# ngptv-lite.net
KiCad netlist of a schematic drawn in EAGLE
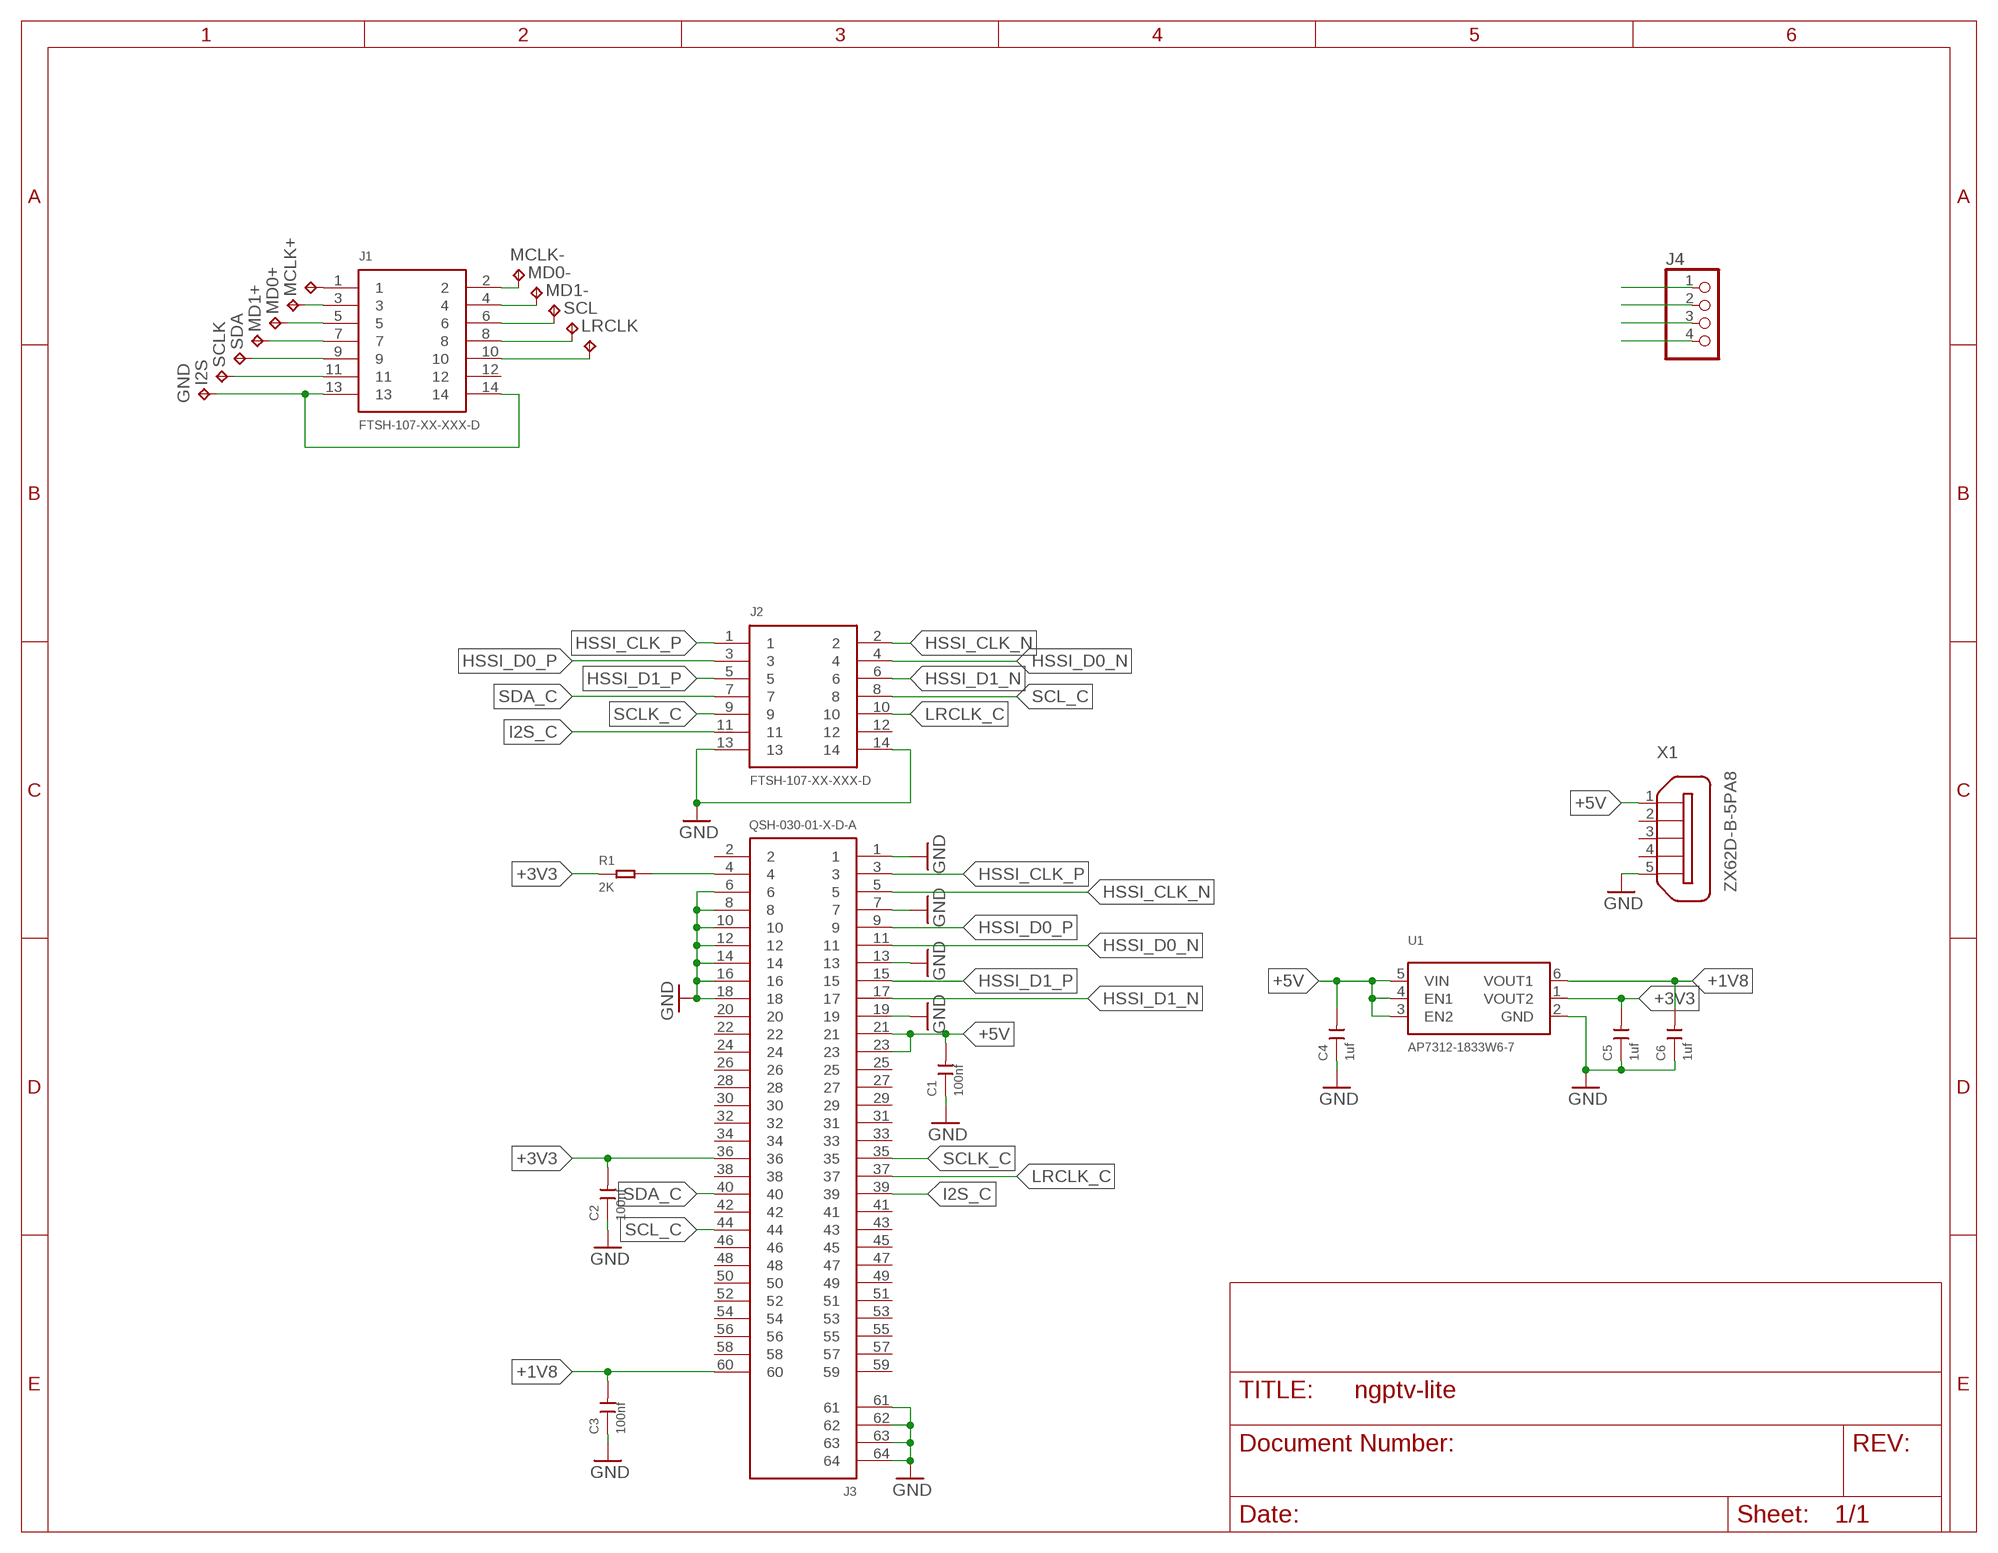
[diagram p0: schematic, sheet 1]

(export (version "E")
  (design (tool "Eeschema 10.0.6"))
  (components
    (comp (ref "C1")
      (value "100nf")
      (footprint "eagle-import:C0603")
      (fields (field (name "MPN") "CC0603KRX7R9BB104"))
      (libsource (lib "eagle-import") (part "CERAMIC-100NF-50V-10%-X7R(0603)"))
    )
    (comp (ref "C2")
      (value "100nf")
      (footprint "eagle-import:C0603")
      (fields (field (name "MPN") "CC0603KRX7R9BB104"))
      (libsource (lib "eagle-import") (part "CERAMIC-100NF-50V-10%-X7R(0603)"))
    )
    (comp (ref "C3")
      (value "100nf")
      (footprint "eagle-import:C0603")
      (fields (field (name "MPN") "CC0603KRX7R9BB104"))
      (libsource (lib "eagle-import") (part "CERAMIC-100NF-50V-10%-X7R(0603)"))
    )
    (comp (ref "C4")
      (value "1uf")
      (footprint "eagle-import:C0603")
      (fields (field (name "MPN") "CC0603KRX7R8BB105"))
      (libsource (lib "eagle-import") (part "CERAMIC-1UF-25V-10%-X7R(0603)"))
    )
    (comp (ref "C5")
      (value "1uf")
      (footprint "eagle-import:C0603")
      (fields (field (name "MPN") "CC0603KRX7R8BB105"))
      (libsource (lib "eagle-import") (part "CERAMIC-1UF-25V-10%-X7R(0603)"))
    )
    (comp (ref "C6")
      (value "1uf")
      (footprint "eagle-import:C0603")
      (fields (field (name "MPN") "CC0603KRX7R8BB105"))
      (libsource (lib "eagle-import") (part "CERAMIC-1UF-25V-10%-X7R(0603)"))
    )
    (comp (ref "GND")
      (value "TPTP14R")
      (footprint "eagle-import:TP14R")
      (libsource (lib "eagle-import") (part "TPTP14R"))
    )
    (comp (ref "I2S")
      (value "TPTP12R")
      (footprint "eagle-import:TP12R")
      (libsource (lib "eagle-import") (part "TPTP12R"))
    )
    (comp (ref "J1")
      (value "FTSH-107-XX-XXX-D")
      (footprint "eagle-import:FTSH-107-XX-XXX-D")
      (libsource (lib "eagle-import") (part "FTSH-107-XX-XXX-D"))
    )
    (comp (ref "J2")
      (value "FTSH-107-XX-XXX-D")
      (footprint "eagle-import:FTSH-107-XX-XXX-D")
      (libsource (lib "eagle-import") (part "FTSH-107-XX-XXX-D"))
    )
    (comp (ref "J3")
      (value "QSH-030-01-X-D-A")
      (footprint "eagle-import:QSH-030-01-X-D-A")
      (libsource (lib "eagle-import") (part "QSH-030-01-X-D-A"))
    )
    (comp (ref "J4")
      (value "PINHD-1X4")
      (footprint "eagle-import:1X04")
      (libsource (lib "eagle-import") (part "PINHD-1X4"))
    )
    (comp (ref "LRCLK")
      (value "TPTP12R")
      (footprint "eagle-import:TP12R")
      (libsource (lib "eagle-import") (part "TPTP12R"))
    )
    (comp (ref "MCLK+")
      (value "TPTP12R")
      (footprint "eagle-import:TP12R")
      (libsource (lib "eagle-import") (part "TPTP12R"))
    )
    (comp (ref "MCLK-")
      (value "TPTP12R")
      (footprint "eagle-import:TP12R")
      (libsource (lib "eagle-import") (part "TPTP12R"))
    )
    (comp (ref "MD0+")
      (value "TPTP12R")
      (footprint "eagle-import:TP12R")
      (libsource (lib "eagle-import") (part "TPTP12R"))
    )
    (comp (ref "MD0-")
      (value "TPTP12R")
      (footprint "eagle-import:TP12R")
      (libsource (lib "eagle-import") (part "TPTP12R"))
    )
    (comp (ref "MD1+")
      (value "TPTP12R")
      (footprint "eagle-import:TP12R")
      (libsource (lib "eagle-import") (part "TPTP12R"))
    )
    (comp (ref "MD1-")
      (value "TPTP12R")
      (footprint "eagle-import:TP12R")
      (libsource (lib "eagle-import") (part "TPTP12R"))
    )
    (comp (ref "R1")
      (value "2K")
      (footprint "eagle-import:R0603")
      (fields (field (name "MPN") "RC0603FR-072KL"))
      (libsource (lib "eagle-import") (part "SMD-RES-2K-1%-1/10W(0603)"))
    )
    (comp (ref "SCL")
      (value "TPTP12R")
      (footprint "eagle-import:TP12R")
      (libsource (lib "eagle-import") (part "TPTP12R"))
    )
    (comp (ref "SCLK")
      (value "TPTP12R")
      (footprint "eagle-import:TP12R")
      (libsource (lib "eagle-import") (part "TPTP12R"))
    )
    (comp (ref "SDA")
      (value "TPTP12R")
      (footprint "eagle-import:TP12R")
      (libsource (lib "eagle-import") (part "TPTP12R"))
    )
    (comp (ref "U1")
      (value "AP7312-1833W6-7")
      (footprint "eagle-import:SOT95P280X145-6N")
      (libsource (lib "eagle-import") (part "AP7312"))
    )
    (comp (ref "X1")
      (value "ZX62D-B-5PA8")
      (footprint "eagle-import:ZX62D-B-5PA8")
      (fields (field (name "MF") "Hirose"))
      (libsource (lib "eagle-import") (part "ZX62D-B-5PA8"))
    )
  )
  (nets
    (net (code "1") (name "+1V8") (class "Default")
      (node (ref "C3") (pin "2") (pinfunction "2_2") (pintype "passive"))
      (node (ref "C6") (pin "2") (pinfunction "2_2") (pintype "passive"))
      (node (ref "J3") (pin "60") (pinfunction "60_60") (pintype "bidirectional"))
      (node (ref "U1") (pin "6") (pinfunction "VOUT1_6") (pintype "power_in"))
    )
    (net (code "2") (name "+3V3") (class "Default")
      (node (ref "C2") (pin "2") (pinfunction "2_2") (pintype "passive"))
      (node (ref "C5") (pin "2") (pinfunction "2_2") (pintype "passive"))
      (node (ref "J3") (pin "36") (pinfunction "36_36") (pintype "bidirectional"))
      (node (ref "R1") (pin "1") (pinfunction "1_1") (pintype "passive"))
      (node (ref "U1") (pin "1") (pinfunction "VOUT2_1") (pintype "power_in"))
    )
    (net (code "3") (name "+5V") (class "Default")
      (node (ref "C1") (pin "2") (pinfunction "2_2") (pintype "passive"))
      (node (ref "C4") (pin "2") (pinfunction "2_2") (pintype "passive"))
      (node (ref "J3") (pin "21") (pinfunction "21_21") (pintype "bidirectional"))
      (node (ref "J3") (pin "23") (pinfunction "23_23") (pintype "bidirectional"))
      (node (ref "J4") (pin "1") (pinfunction "1_1") (pintype "passive"))
      (node (ref "U1") (pin "3") (pinfunction "EN2_3") (pintype "bidirectional"))
      (node (ref "U1") (pin "4") (pinfunction "EN1_4") (pintype "bidirectional"))
      (node (ref "U1") (pin "5") (pinfunction "VIN_5") (pintype "power_in"))
      (node (ref "X1") (pin "1") (pinfunction "1_1") (pintype "passive"))
    )
    (net (code "4") (name "GND") (class "Default")
      (node (ref "C1") (pin "1") (pinfunction "1_1") (pintype "passive"))
      (node (ref "C2") (pin "1") (pinfunction "1_1") (pintype "passive"))
      (node (ref "C3") (pin "1") (pinfunction "1_1") (pintype "passive"))
      (node (ref "C4") (pin "1") (pinfunction "1_1") (pintype "passive"))
      (node (ref "C5") (pin "1") (pinfunction "1_1") (pintype "passive"))
      (node (ref "C6") (pin "1") (pinfunction "1_1") (pintype "passive"))
      (node (ref "J2") (pin "13") (pinfunction "13_13") (pintype "bidirectional"))
      (node (ref "J2") (pin "14") (pinfunction "14_14") (pintype "bidirectional"))
      (node (ref "J3") (pin "1") (pinfunction "1_1") (pintype "bidirectional"))
      (node (ref "J3") (pin "10") (pinfunction "10_10") (pintype "bidirectional"))
      (node (ref "J3") (pin "12") (pinfunction "12_12") (pintype "bidirectional"))
      (node (ref "J3") (pin "13") (pinfunction "13_13") (pintype "bidirectional"))
      (node (ref "J3") (pin "14") (pinfunction "14_14") (pintype "bidirectional"))
      (node (ref "J3") (pin "16") (pinfunction "16_16") (pintype "bidirectional"))
      (node (ref "J3") (pin "18") (pinfunction "18_18") (pintype "bidirectional"))
      (node (ref "J3") (pin "19") (pinfunction "19_19") (pintype "bidirectional"))
      (node (ref "J3") (pin "6") (pinfunction "6_6") (pintype "bidirectional"))
      (node (ref "J3") (pin "61") (pinfunction "61_61") (pintype "power_in"))
      (node (ref "J3") (pin "62") (pinfunction "62_62") (pintype "power_in"))
      (node (ref "J3") (pin "63") (pinfunction "63_63") (pintype "power_in"))
      (node (ref "J3") (pin "64") (pinfunction "64_64") (pintype "power_in"))
      (node (ref "J3") (pin "7") (pinfunction "7_7") (pintype "bidirectional"))
      (node (ref "J3") (pin "8") (pinfunction "8_8") (pintype "bidirectional"))
      (node (ref "J4") (pin "2") (pinfunction "2_2") (pintype "passive"))
      (node (ref "U1") (pin "2") (pinfunction "GND_2") (pintype "bidirectional"))
      (node (ref "X1") (pin "5") (pinfunction "5_5") (pintype "passive"))
    )
    (net (code "5") (name "HSSI_CLK_N") (class "Default")
      (node (ref "J2") (pin "2") (pinfunction "2_2") (pintype "bidirectional"))
      (node (ref "J3") (pin "5") (pinfunction "5_5") (pintype "bidirectional"))
    )
    (net (code "6") (name "HSSI_CLK_P") (class "Default")
      (node (ref "J2") (pin "1") (pinfunction "1_1") (pintype "bidirectional"))
      (node (ref "J3") (pin "3") (pinfunction "3_3") (pintype "bidirectional"))
    )
    (net (code "7") (name "HSSI_D0_N") (class "Default")
      (node (ref "J2") (pin "4") (pinfunction "4_4") (pintype "bidirectional"))
      (node (ref "J3") (pin "11") (pinfunction "11_11") (pintype "bidirectional"))
    )
    (net (code "8") (name "HSSI_D0_P") (class "Default")
      (node (ref "J2") (pin "3") (pinfunction "3_3") (pintype "bidirectional"))
      (node (ref "J3") (pin "9") (pinfunction "9_9") (pintype "bidirectional"))
    )
    (net (code "9") (name "HSSI_D1_N") (class "Default")
      (node (ref "J2") (pin "6") (pinfunction "6_6") (pintype "bidirectional"))
      (node (ref "J3") (pin "17") (pinfunction "17_17") (pintype "bidirectional"))
    )
    (net (code "10") (name "HSSI_D1_P") (class "Default")
      (node (ref "J2") (pin "5") (pinfunction "5_5") (pintype "bidirectional"))
      (node (ref "J3") (pin "15") (pinfunction "15_15") (pintype "bidirectional"))
    )
    (net (code "11") (name "I2S_C") (class "Default")
      (node (ref "J2") (pin "11") (pinfunction "11_11") (pintype "bidirectional"))
      (node (ref "J3") (pin "39") (pinfunction "39_39") (pintype "bidirectional"))
    )
    (net (code "12") (name "LRCLK_C") (class "Default")
      (node (ref "J2") (pin "10") (pinfunction "10_10") (pintype "bidirectional"))
      (node (ref "J3") (pin "37") (pinfunction "37_37") (pintype "bidirectional"))
    )
    (net (code "13") (name "Net-(GND-PadTP)") (class "Default")
      (node (ref "GND") (pin "TP") (pinfunction "TP_TP") (pintype "input"))
      (node (ref "J1") (pin "13") (pinfunction "13_13") (pintype "bidirectional"))
      (node (ref "J1") (pin "14") (pinfunction "14_14") (pintype "bidirectional"))
    )
    (net (code "14") (name "Net-(I2S-PadTP)") (class "Default")
      (node (ref "I2S") (pin "TP") (pinfunction "TP_TP") (pintype "input"))
      (node (ref "J1") (pin "11") (pinfunction "11_11") (pintype "bidirectional"))
    )
    (net (code "15") (name "Net-(J1-Pad1)") (class "Default")
      (node (ref "J1") (pin "1") (pinfunction "1_1") (pintype "bidirectional"))
      (node (ref "MCLK+") (pin "TP") (pinfunction "TP_TP") (pintype "input"))
    )
    (net (code "16") (name "Net-(J1-Pad2)") (class "Default")
      (node (ref "J1") (pin "2") (pinfunction "2_2") (pintype "bidirectional"))
      (node (ref "MCLK-") (pin "TP") (pinfunction "TP_TP") (pintype "input"))
    )
    (net (code "17") (name "Net-(J1-Pad3)") (class "Default")
      (node (ref "J1") (pin "3") (pinfunction "3_3") (pintype "bidirectional"))
      (node (ref "MD0+") (pin "TP") (pinfunction "TP_TP") (pintype "input"))
    )
    (net (code "18") (name "Net-(J1-Pad4)") (class "Default")
      (node (ref "J1") (pin "4") (pinfunction "4_4") (pintype "bidirectional"))
      (node (ref "MD0-") (pin "TP") (pinfunction "TP_TP") (pintype "input"))
    )
    (net (code "19") (name "Net-(J1-Pad5)") (class "Default")
      (node (ref "J1") (pin "5") (pinfunction "5_5") (pintype "bidirectional"))
      (node (ref "MD1+") (pin "TP") (pinfunction "TP_TP") (pintype "input"))
    )
    (net (code "20") (name "Net-(J1-Pad6)") (class "Default")
      (node (ref "J1") (pin "6") (pinfunction "6_6") (pintype "bidirectional"))
      (node (ref "MD1-") (pin "TP") (pinfunction "TP_TP") (pintype "input"))
    )
    (net (code "21") (name "Net-(J1-Pad7)") (class "Default")
      (node (ref "J1") (pin "7") (pinfunction "7_7") (pintype "bidirectional"))
      (node (ref "SDA") (pin "TP") (pinfunction "TP_TP") (pintype "input"))
    )
    (net (code "22") (name "Net-(J1-Pad8)") (class "Default")
      (node (ref "J1") (pin "8") (pinfunction "8_8") (pintype "bidirectional"))
      (node (ref "SCL") (pin "TP") (pinfunction "TP_TP") (pintype "input"))
    )
    (net (code "23") (name "Net-(J1-Pad9)") (class "Default")
      (node (ref "J1") (pin "9") (pinfunction "9_9") (pintype "bidirectional"))
      (node (ref "SCLK") (pin "TP") (pinfunction "TP_TP") (pintype "input"))
    )
    (net (code "24") (name "Net-(J1-Pad10)") (class "Default")
      (node (ref "J1") (pin "10") (pinfunction "10_10") (pintype "bidirectional"))
      (node (ref "LRCLK") (pin "TP") (pinfunction "TP_TP") (pintype "input"))
    )
    (net (code "25") (name "Net-(J3-Pad4)") (class "Default")
      (node (ref "J3") (pin "4") (pinfunction "4_4") (pintype "bidirectional"))
      (node (ref "R1") (pin "2") (pinfunction "2_2") (pintype "passive"))
    )
    (net (code "26") (name "SCLK_C") (class "Default")
      (node (ref "J2") (pin "9") (pinfunction "9_9") (pintype "bidirectional"))
      (node (ref "J3") (pin "35") (pinfunction "35_35") (pintype "bidirectional"))
    )
    (net (code "27") (name "SCL_C") (class "Default")
      (node (ref "J2") (pin "8") (pinfunction "8_8") (pintype "bidirectional"))
      (node (ref "J3") (pin "44") (pinfunction "44_44") (pintype "bidirectional"))
      (node (ref "J4") (pin "4") (pinfunction "4_4") (pintype "passive"))
    )
    (net (code "28") (name "SDA_C") (class "Default")
      (node (ref "J2") (pin "7") (pinfunction "7_7") (pintype "bidirectional"))
      (node (ref "J3") (pin "40") (pinfunction "40_40") (pintype "bidirectional"))
      (node (ref "J4") (pin "3") (pinfunction "3_3") (pintype "passive"))
    )
    (net (code "29") (name "unconnected-(J1-Pad12)") (class "Default")
      (node (ref "J1") (pin "12") (pinfunction "12_12") (pintype "bidirectional"))
    )
    (net (code "30") (name "unconnected-(J2-Pad12)") (class "Default")
      (node (ref "J2") (pin "12") (pinfunction "12_12") (pintype "bidirectional"))
    )
    (net (code "31") (name "unconnected-(J3-Pad2)") (class "Default")
      (node (ref "J3") (pin "2") (pinfunction "2_2") (pintype "bidirectional"))
    )
    (net (code "32") (name "unconnected-(J3-Pad20)") (class "Default")
      (node (ref "J3") (pin "20") (pinfunction "20_20") (pintype "bidirectional"))
    )
    (net (code "33") (name "unconnected-(J3-Pad22)") (class "Default")
      (node (ref "J3") (pin "22") (pinfunction "22_22") (pintype "bidirectional"))
    )
    (net (code "34") (name "unconnected-(J3-Pad24)") (class "Default")
      (node (ref "J3") (pin "24") (pinfunction "24_24") (pintype "bidirectional"))
    )
    (net (code "35") (name "unconnected-(J3-Pad25)") (class "Default")
      (node (ref "J3") (pin "25") (pinfunction "25_25") (pintype "bidirectional"))
    )
    (net (code "36") (name "unconnected-(J3-Pad26)") (class "Default")
      (node (ref "J3") (pin "26") (pinfunction "26_26") (pintype "bidirectional"))
    )
    (net (code "37") (name "unconnected-(J3-Pad27)") (class "Default")
      (node (ref "J3") (pin "27") (pinfunction "27_27") (pintype "bidirectional"))
    )
    (net (code "38") (name "unconnected-(J3-Pad28)") (class "Default")
      (node (ref "J3") (pin "28") (pinfunction "28_28") (pintype "bidirectional"))
    )
    (net (code "39") (name "unconnected-(J3-Pad29)") (class "Default")
      (node (ref "J3") (pin "29") (pinfunction "29_29") (pintype "bidirectional"))
    )
    (net (code "40") (name "unconnected-(J3-Pad30)") (class "Default")
      (node (ref "J3") (pin "30") (pinfunction "30_30") (pintype "bidirectional"))
    )
    (net (code "41") (name "unconnected-(J3-Pad31)") (class "Default")
      (node (ref "J3") (pin "31") (pinfunction "31_31") (pintype "bidirectional"))
    )
    (net (code "42") (name "unconnected-(J3-Pad32)") (class "Default")
      (node (ref "J3") (pin "32") (pinfunction "32_32") (pintype "bidirectional"))
    )
    (net (code "43") (name "unconnected-(J3-Pad33)") (class "Default")
      (node (ref "J3") (pin "33") (pinfunction "33_33") (pintype "bidirectional"))
    )
    (net (code "44") (name "unconnected-(J3-Pad34)") (class "Default")
      (node (ref "J3") (pin "34") (pinfunction "34_34") (pintype "bidirectional"))
    )
    (net (code "45") (name "unconnected-(J3-Pad38)") (class "Default")
      (node (ref "J3") (pin "38") (pinfunction "38_38") (pintype "bidirectional"))
    )
    (net (code "46") (name "unconnected-(J3-Pad41)") (class "Default")
      (node (ref "J3") (pin "41") (pinfunction "41_41") (pintype "bidirectional"))
    )
    (net (code "47") (name "unconnected-(J3-Pad42)") (class "Default")
      (node (ref "J3") (pin "42") (pinfunction "42_42") (pintype "bidirectional"))
    )
    (net (code "48") (name "unconnected-(J3-Pad43)") (class "Default")
      (node (ref "J3") (pin "43") (pinfunction "43_43") (pintype "bidirectional"))
    )
    (net (code "49") (name "unconnected-(J3-Pad45)") (class "Default")
      (node (ref "J3") (pin "45") (pinfunction "45_45") (pintype "bidirectional"))
    )
    (net (code "50") (name "unconnected-(J3-Pad46)") (class "Default")
      (node (ref "J3") (pin "46") (pinfunction "46_46") (pintype "bidirectional"))
    )
    (net (code "51") (name "unconnected-(J3-Pad47)") (class "Default")
      (node (ref "J3") (pin "47") (pinfunction "47_47") (pintype "bidirectional"))
    )
    (net (code "52") (name "unconnected-(J3-Pad48)") (class "Default")
      (node (ref "J3") (pin "48") (pinfunction "48_48") (pintype "bidirectional"))
    )
    (net (code "53") (name "unconnected-(J3-Pad49)") (class "Default")
      (node (ref "J3") (pin "49") (pinfunction "49_49") (pintype "bidirectional"))
    )
    (net (code "54") (name "unconnected-(J3-Pad50)") (class "Default")
      (node (ref "J3") (pin "50") (pinfunction "50_50") (pintype "bidirectional"))
    )
    (net (code "55") (name "unconnected-(J3-Pad51)") (class "Default")
      (node (ref "J3") (pin "51") (pinfunction "51_51") (pintype "bidirectional"))
    )
    (net (code "56") (name "unconnected-(J3-Pad52)") (class "Default")
      (node (ref "J3") (pin "52") (pinfunction "52_52") (pintype "bidirectional"))
    )
    (net (code "57") (name "unconnected-(J3-Pad53)") (class "Default")
      (node (ref "J3") (pin "53") (pinfunction "53_53") (pintype "bidirectional"))
    )
    (net (code "58") (name "unconnected-(J3-Pad54)") (class "Default")
      (node (ref "J3") (pin "54") (pinfunction "54_54") (pintype "bidirectional"))
    )
    (net (code "59") (name "unconnected-(J3-Pad55)") (class "Default")
      (node (ref "J3") (pin "55") (pinfunction "55_55") (pintype "bidirectional"))
    )
    (net (code "60") (name "unconnected-(J3-Pad56)") (class "Default")
      (node (ref "J3") (pin "56") (pinfunction "56_56") (pintype "bidirectional"))
    )
    (net (code "61") (name "unconnected-(J3-Pad57)") (class "Default")
      (node (ref "J3") (pin "57") (pinfunction "57_57") (pintype "bidirectional"))
    )
    (net (code "62") (name "unconnected-(J3-Pad58)") (class "Default")
      (node (ref "J3") (pin "58") (pinfunction "58_58") (pintype "bidirectional"))
    )
    (net (code "63") (name "unconnected-(J3-Pad59)") (class "Default")
      (node (ref "J3") (pin "59") (pinfunction "59_59") (pintype "bidirectional"))
    )
    (net (code "64") (name "unconnected-(X1-Pad2)") (class "Default")
      (node (ref "X1") (pin "2") (pinfunction "2_2") (pintype "passive"))
    )
    (net (code "65") (name "unconnected-(X1-Pad3)") (class "Default")
      (node (ref "X1") (pin "3") (pinfunction "3_3") (pintype "passive"))
    )
    (net (code "66") (name "unconnected-(X1-Pad4)") (class "Default")
      (node (ref "X1") (pin "4") (pinfunction "4_4") (pintype "passive"))
    )
  )
)
